# USB.net
KiCad netlist of a schematic drawn in Altium Designer
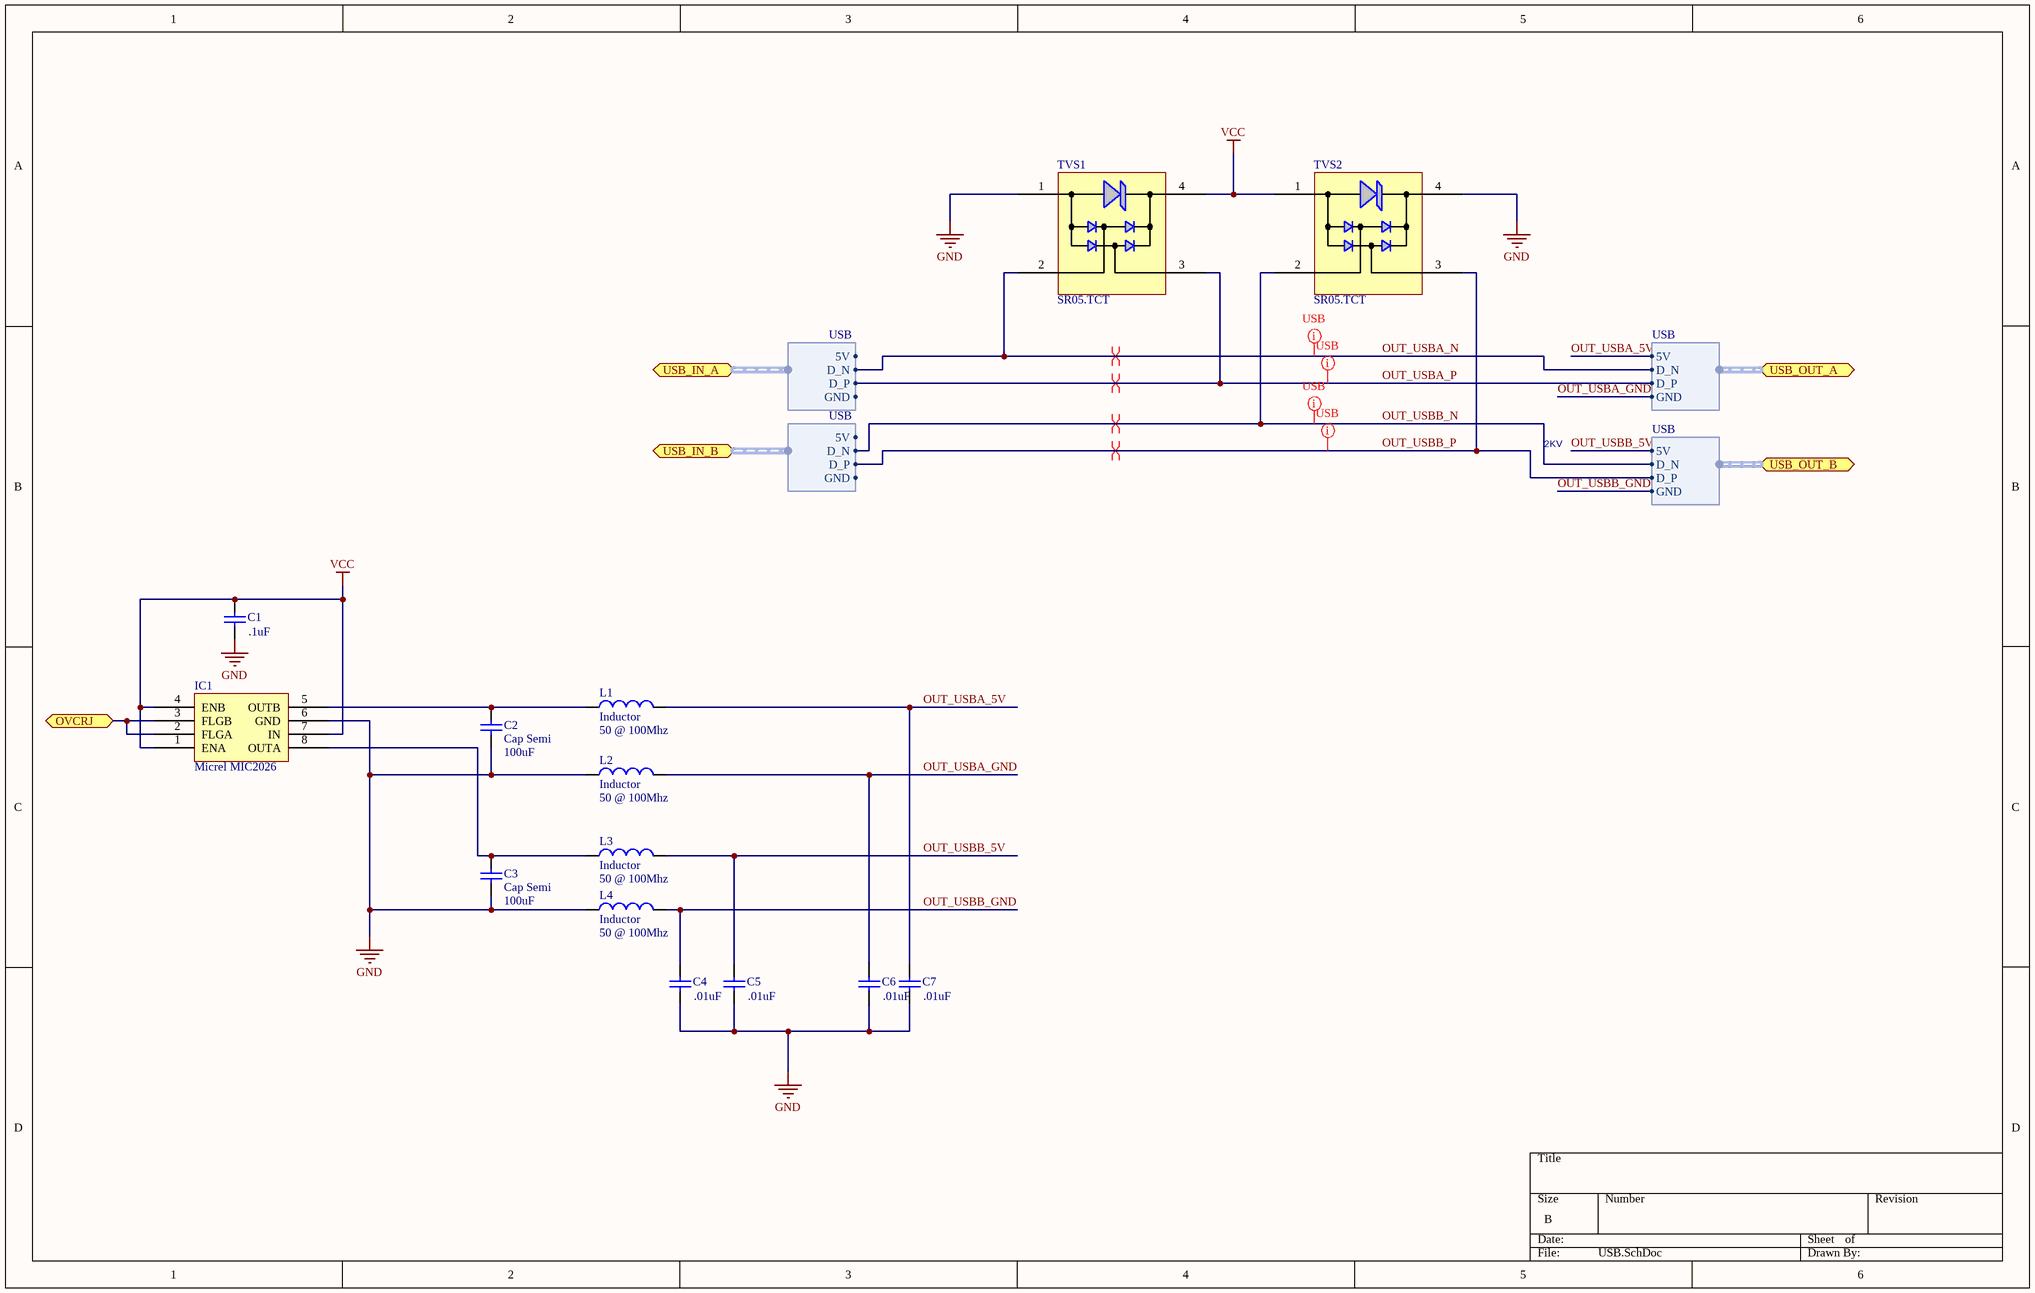
[diagram p0: USB.SchDoc]

(export (version "E")
  (design (tool "Eeschema 10.0.6"))
  (components
    (comp (ref "C1")
      (value ".1uF")
      (footprint "0402")
      (description "Capacitor (Semiconductor SIM Model)")
      (fields (field (name "Comment") "Cap Semi") (field (name "PUBLISHER") "Altium Limited"))
      (libsource (lib "Miscellaneous Devices") (part "Cap Semi"))
    )
    (comp (ref "C2")
      (value "Cap Semi")
      (footprint "C1210")
      (description "Capacitor (Semiconductor SIM Model)")
      (fields (field (name "ALTIUM_VALUE") "100uF") (field (name "PUBLISHER") "Altium Limited"))
      (libsource (lib "Miscellaneous Devices") (part "Cap Semi"))
    )
    (comp (ref "C3")
      (value "Cap Semi")
      (footprint "C1210")
      (description "Capacitor (Semiconductor SIM Model)")
      (fields (field (name "ALTIUM_VALUE") "100uF") (field (name "PUBLISHER") "Altium Limited"))
      (libsource (lib "Miscellaneous Devices") (part "Cap Semi"))
    )
    (comp (ref "C4")
      (value ".01uF")
      (footprint "0402")
      (description "Capacitor (Semiconductor SIM Model)")
      (fields (field (name "Comment") "Cap Semi") (field (name "PUBLISHER") "Altium Limited"))
      (libsource (lib "Miscellaneous Devices") (part "Cap Semi"))
    )
    (comp (ref "C5")
      (value ".01uF")
      (footprint "0402")
      (description "Capacitor (Semiconductor SIM Model)")
      (fields (field (name "Comment") "Cap Semi") (field (name "PUBLISHER") "Altium Limited"))
      (libsource (lib "Miscellaneous Devices") (part "Cap Semi"))
    )
    (comp (ref "C6")
      (value ".01uF")
      (footprint "0402")
      (description "Capacitor (Semiconductor SIM Model)")
      (fields (field (name "Comment") "Cap Semi") (field (name "PUBLISHER") "Altium Limited"))
      (libsource (lib "Miscellaneous Devices") (part "Cap Semi"))
    )
    (comp (ref "C7")
      (value ".01uF")
      (footprint "0402")
      (description "Capacitor (Semiconductor SIM Model)")
      (fields (field (name "Comment") "Cap Semi") (field (name "PUBLISHER") "Altium Limited"))
      (libsource (lib "Miscellaneous Devices") (part "Cap Semi"))
    )
    (comp (ref "IC1")
      (value "Micrel MIC2026")
      (footprint "Micrel:8-Pin SOIC")
      (description "Micrel MIC2026 Dual-Channel Power Distribution Switch")
      (libsource (lib "MIC2026") (part "MIC2026"))
    )
    (comp (ref "L1")
      (value "Inductor")
      (footprint "0402-A")
      (fields (field (name "ALTIUM_VALUE") "50 @ 100Mhz") (field (name "PUBLISHER") "Altium Limited"))
      (libsource (lib "Miscellaneous Devices") (part "Inductor"))
    )
    (comp (ref "L2")
      (value "Inductor")
      (footprint "0402-A")
      (fields (field (name "ALTIUM_VALUE") "50 @ 100Mhz") (field (name "PUBLISHER") "Altium Limited"))
      (libsource (lib "Miscellaneous Devices") (part "Inductor"))
    )
    (comp (ref "L3")
      (value "Inductor")
      (footprint "0402-A")
      (fields (field (name "ALTIUM_VALUE") "50 @ 100Mhz") (field (name "PUBLISHER") "Altium Limited"))
      (libsource (lib "Miscellaneous Devices") (part "Inductor"))
    )
    (comp (ref "L4")
      (value "Inductor")
      (footprint "0402-A")
      (fields (field (name "ALTIUM_VALUE") "50 @ 100Mhz") (field (name "PUBLISHER") "Altium Limited"))
      (libsource (lib "Miscellaneous Devices") (part "Inductor"))
    )
    (comp (ref "TVS1")
      (value "SR05.TCT")
      (footprint "IPC-SM-782 Section 8.9 SOT143:SOT143")
      (description "IC TVS ARRAY 2-LINE 5V SOT-143")
      (libsource (lib "TVS Arrays") (part "SR05.TCT"))
    )
    (comp (ref "TVS2")
      (value "SR05.TCT")
      (footprint "IPC-SM-782 Section 8.9 SOT143:SOT143")
      (description "IC TVS ARRAY 2-LINE 5V SOT-143")
      (libsource (lib "TVS Arrays") (part "SR05.TCT"))
    )
  )
  (nets
    (net (code "2") (name "/OUT_USBA_5V") (class "Default")
      (node (ref "C7") (pin "2") (pinfunction "2_2") (pintype "passive"))
      (node (ref "L1") (pin "2") (pinfunction "2_2") (pintype "passive"))
    )
    (net (code "3") (name "/OUT_USBA_GND") (class "Default")
      (node (ref "C6") (pin "2") (pinfunction "2_2") (pintype "passive"))
      (node (ref "L2") (pin "2") (pinfunction "2_2") (pintype "passive"))
    )
    (net (code "4") (name "/OUT_USBA_N") (class "Default")
      (node (ref "TVS1") (pin "2") (pinfunction "2_2") (pintype "passive"))
    )
    (net (code "5") (name "/OUT_USBA_P") (class "Default")
      (node (ref "TVS1") (pin "3") (pinfunction "3_3") (pintype "passive"))
    )
    (net (code "6") (name "/OUT_USBB_5V") (class "Default")
      (node (ref "C5") (pin "2") (pinfunction "2_2") (pintype "passive"))
      (node (ref "L3") (pin "2") (pinfunction "2_2") (pintype "passive"))
    )
    (net (code "7") (name "/OUT_USBB_GND") (class "Default")
      (node (ref "C4") (pin "2") (pinfunction "2_2") (pintype "passive"))
      (node (ref "L4") (pin "2") (pinfunction "2_2") (pintype "passive"))
    )
    (net (code "8") (name "/OUT_USBB_N") (class "Default")
      (node (ref "TVS2") (pin "2") (pinfunction "2_2") (pintype "passive"))
    )
    (net (code "9") (name "/OUT_USBB_P") (class "Default")
      (node (ref "TVS2") (pin "3") (pinfunction "3_3") (pintype "passive"))
    )
    (net (code "10") (name "/OVCRJ") (class "Default")
      (node (ref "IC1") (pin "2") (pinfunction "FLGA_2") (pintype "passive"))
      (node (ref "IC1") (pin "3") (pinfunction "FLGB_3") (pintype "passive"))
    )
    (net (code "12") (name "GND") (class "Default")
      (node (ref "C1") (pin "1") (pinfunction "1_1") (pintype "passive"))
      (node (ref "C2") (pin "1") (pinfunction "1_1") (pintype "passive"))
      (node (ref "C3") (pin "1") (pinfunction "1_1") (pintype "passive"))
      (node (ref "C4") (pin "1") (pinfunction "1_1") (pintype "passive"))
      (node (ref "C5") (pin "1") (pinfunction "1_1") (pintype "passive"))
      (node (ref "C6") (pin "1") (pinfunction "1_1") (pintype "passive"))
      (node (ref "C7") (pin "1") (pinfunction "1_1") (pintype "passive"))
      (node (ref "IC1") (pin "6") (pinfunction "GND_6") (pintype "passive"))
      (node (ref "L2") (pin "1") (pinfunction "1_1") (pintype "passive"))
      (node (ref "L4") (pin "1") (pinfunction "1_1") (pintype "passive"))
      (node (ref "TVS1") (pin "1") (pinfunction "1_1") (pintype "passive"))
      (node (ref "TVS2") (pin "4") (pinfunction "4_4") (pintype "passive"))
    )
    (net (code "13") (name "Net-(IC1-OUTA)") (class "Default")
      (node (ref "C3") (pin "2") (pinfunction "2_2") (pintype "passive"))
      (node (ref "IC1") (pin "8") (pinfunction "OUTA_8") (pintype "passive"))
      (node (ref "L3") (pin "1") (pinfunction "1_1") (pintype "passive"))
    )
    (net (code "14") (name "Net-(IC1-OUTB)") (class "Default")
      (node (ref "C2") (pin "2") (pinfunction "2_2") (pintype "passive"))
      (node (ref "IC1") (pin "5") (pinfunction "OUTB_5") (pintype "passive"))
      (node (ref "L1") (pin "1") (pinfunction "1_1") (pintype "passive"))
    )
    (net (code "15") (name "VCC") (class "Default")
      (node (ref "C1") (pin "2") (pinfunction "2_2") (pintype "passive"))
      (node (ref "IC1") (pin "1") (pinfunction "ENA_1") (pintype "passive"))
      (node (ref "IC1") (pin "4") (pinfunction "ENB_4") (pintype "passive"))
      (node (ref "IC1") (pin "7") (pinfunction "IN_7") (pintype "passive"))
      (node (ref "TVS1") (pin "4") (pinfunction "4_4") (pintype "passive"))
      (node (ref "TVS2") (pin "1") (pinfunction "1_1") (pintype "passive"))
    )
  )
)
